# POWER_SUPPLY_BOARD.net
KiCad netlist of a schematic drawn in EAGLE
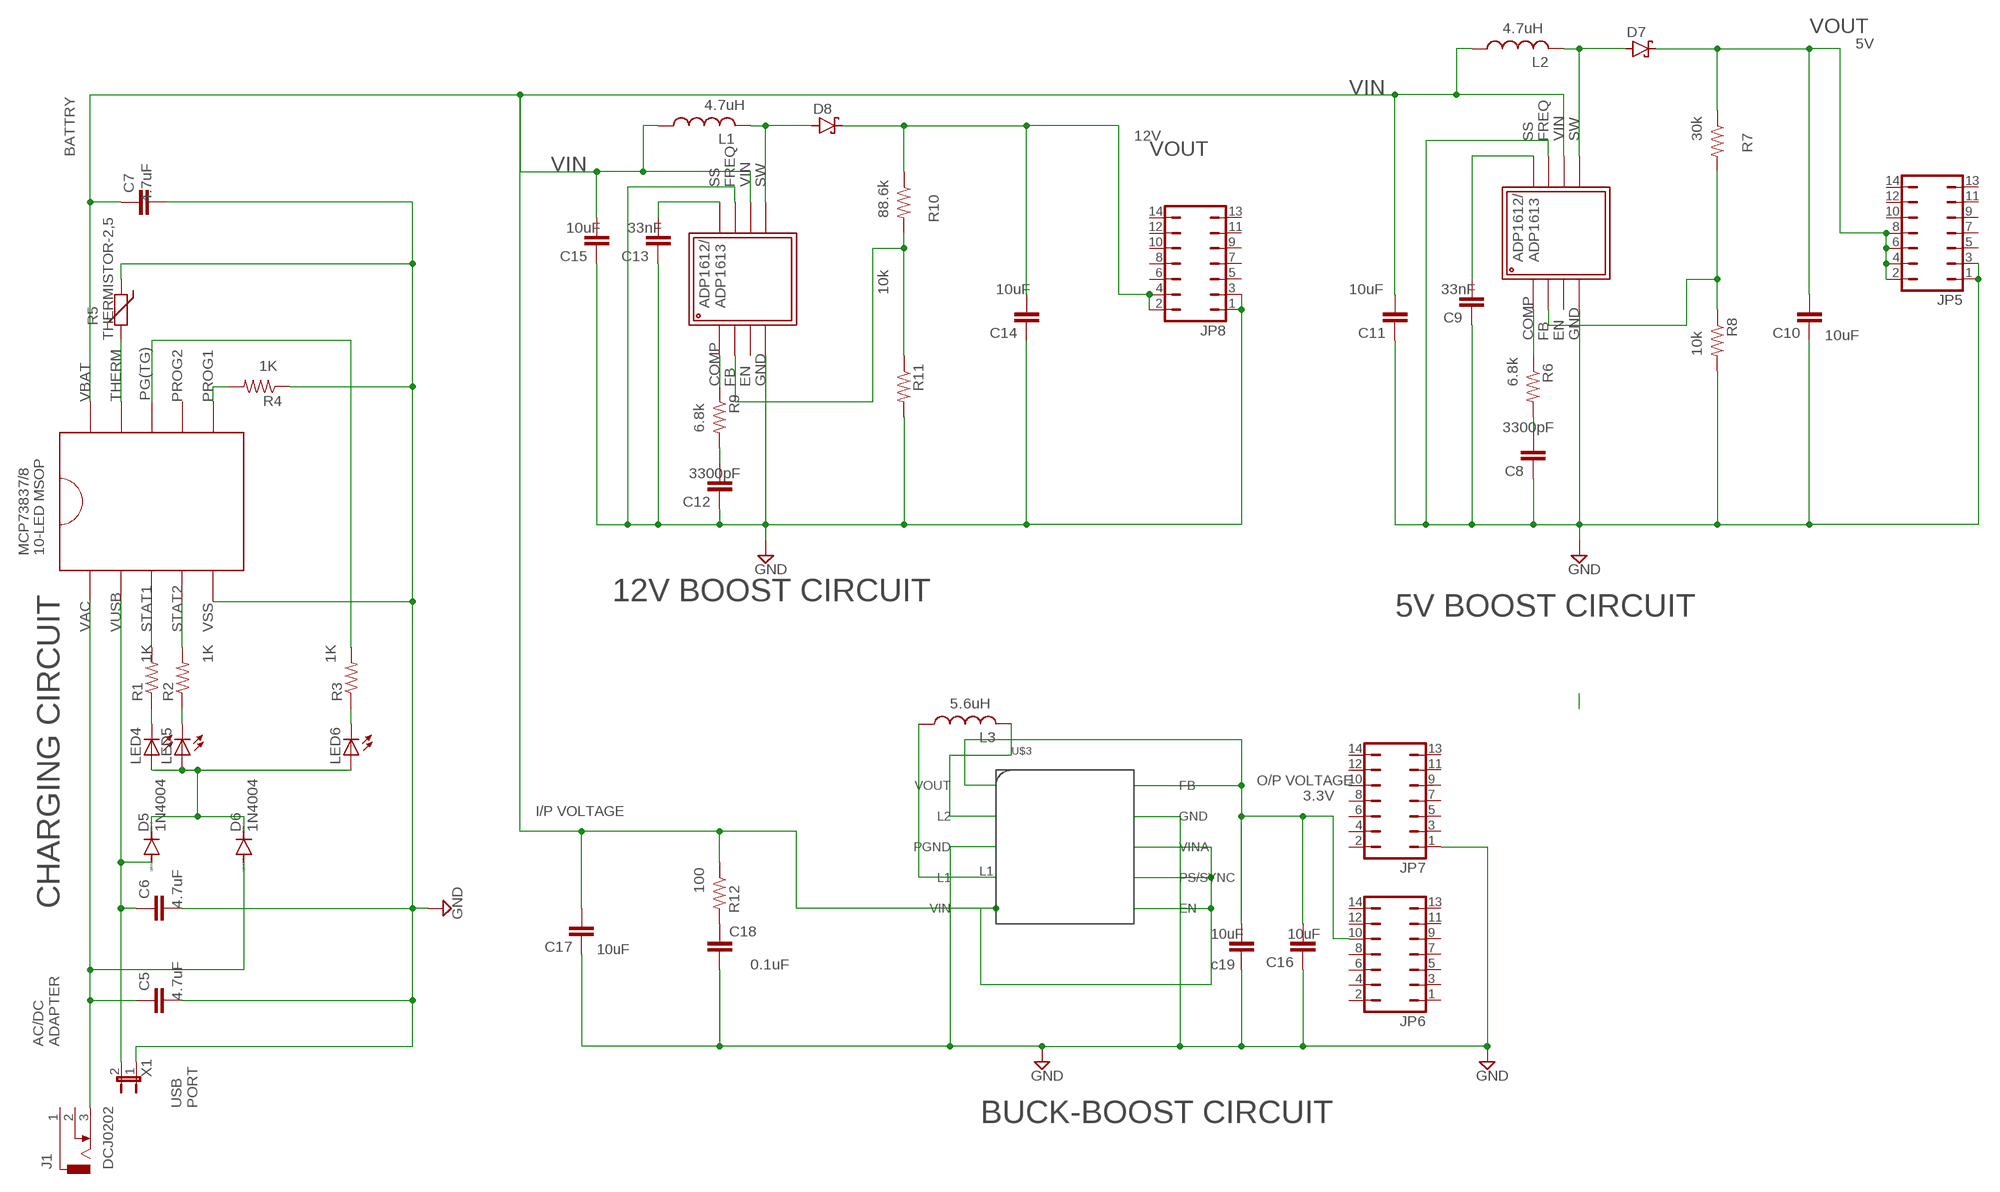
[diagram p0: schematic, sheet 1]

(export (version "E")
  (design (tool "Eeschema 10.0.6"))
  (components
    (comp (ref "C1")
      (value "C2,5-3")
      (footprint "eagle-import:C2.5-3")
      (libsource (lib "eagle-import") (part "C2,5-3"))
    )
    (comp (ref "C5")
      (value "C2.5/5")
      (footprint "eagle-import:C2.5-5")
      (libsource (lib "eagle-import") (part "C2.5/5"))
    )
    (comp (ref "C6")
      (value "C2.5/5")
      (footprint "eagle-import:C2.5-5")
      (libsource (lib "eagle-import") (part "C2.5/5"))
    )
    (comp (ref "C7")
      (value "C2.5/5")
      (footprint "eagle-import:C2.5-5")
      (libsource (lib "eagle-import") (part "C2.5/5"))
    )
    (comp (ref "C8")
      (value "C2,5-3")
      (footprint "eagle-import:C2.5-3")
      (libsource (lib "eagle-import") (part "C2,5-3"))
    )
    (comp (ref "C9")
      (value "C2,5-3")
      (footprint "eagle-import:C2.5-3")
      (libsource (lib "eagle-import") (part "C2,5-3"))
    )
    (comp (ref "C10")
      (value "C2,5-3")
      (footprint "eagle-import:C2.5-3")
      (libsource (lib "eagle-import") (part "C2,5-3"))
    )
    (comp (ref "C11")
      (value "C2,5-3")
      (footprint "eagle-import:C2.5-3")
      (libsource (lib "eagle-import") (part "C2,5-3"))
    )
    (comp (ref "C12")
      (value "C2,5-3")
      (footprint "eagle-import:C2.5-3")
      (libsource (lib "eagle-import") (part "C2,5-3"))
    )
    (comp (ref "C13")
      (value "C2,5-3")
      (footprint "eagle-import:C2.5-3")
      (libsource (lib "eagle-import") (part "C2,5-3"))
    )
    (comp (ref "C14")
      (value "C2,5-3")
      (footprint "eagle-import:C2.5-3")
      (libsource (lib "eagle-import") (part "C2,5-3"))
    )
    (comp (ref "C15")
      (value "C2,5-3")
      (footprint "eagle-import:C2.5-3")
      (libsource (lib "eagle-import") (part "C2,5-3"))
    )
    (comp (ref "C16")
      (value "C2,5-3")
      (footprint "eagle-import:C2.5-3")
      (libsource (lib "eagle-import") (part "C2,5-3"))
    )
    (comp (ref "C17")
      (value "C2,5-3")
      (footprint "eagle-import:C2.5-3")
      (libsource (lib "eagle-import") (part "C2,5-3"))
    )
    (comp (ref "C18")
      (value "C2,5-3")
      (footprint "eagle-import:C2.5-3")
      (libsource (lib "eagle-import") (part "C2,5-3"))
    )
    (comp (ref "D5")
      (value "1N4004")
      (footprint "eagle-import:DO41-10")
      (libsource (lib "eagle-import") (part "1N4004"))
    )
    (comp (ref "D6")
      (value "1N4004")
      (footprint "eagle-import:DO41-10")
      (libsource (lib "eagle-import") (part "1N4004"))
    )
    (comp (ref "D7")
      (value "SCHOTTKY-DIODEC4111-15")
      (footprint "eagle-import:C4111-15")
      (libsource (lib "eagle-import") (part "SCHOTTKY-DIODEC4111-15"))
    )
    (comp (ref "D8")
      (value "SCHOTTKY-DIODEC4111-15")
      (footprint "eagle-import:C4111-15")
      (libsource (lib "eagle-import") (part "SCHOTTKY-DIODEC4111-15"))
    )
    (comp (ref "J1")
      (value "DCJ0202")
      (footprint "eagle-import:DCJ0202")
      (libsource (lib "eagle-import") (part "DCJ0202"))
    )
    (comp (ref "JP1")
      (value "JP1E")
      (footprint "eagle-import:JP1")
      (libsource (lib "eagle-import") (part "JP1E"))
    )
    (comp (ref "JP5")
      (value "JP7Q")
      (footprint "eagle-import:JP7Q")
      (libsource (lib "eagle-import") (part "JP7Q"))
    )
    (comp (ref "JP6")
      (value "JP7Q")
      (footprint "eagle-import:JP7Q")
      (libsource (lib "eagle-import") (part "JP7Q"))
    )
    (comp (ref "JP7")
      (value "JP7Q")
      (footprint "eagle-import:JP7Q")
      (libsource (lib "eagle-import") (part "JP7Q"))
    )
    (comp (ref "JP8")
      (value "JP7Q")
      (footprint "eagle-import:JP7Q")
      (libsource (lib "eagle-import") (part "JP7Q"))
    )
    (comp (ref "L1")
      (value "L-US0204/5")
      (footprint "eagle-import:0204_5")
      (libsource (lib "eagle-import") (part "L-US0204/5"))
    )
    (comp (ref "L2")
      (value "L-US0204/5")
      (footprint "eagle-import:0204_5")
      (libsource (lib "eagle-import") (part "L-US0204/5"))
    )
    (comp (ref "L3")
      (value "L-US0204/5")
      (footprint "eagle-import:0204_5")
      (libsource (lib "eagle-import") (part "L-US0204/5"))
    )
    (comp (ref "LED4")
      (value "LED3MM")
      (footprint "eagle-import:LED3MM")
      (libsource (lib "eagle-import") (part "LED3MM"))
    )
    (comp (ref "LED5")
      (value "LED3MM")
      (footprint "eagle-import:LED3MM")
      (libsource (lib "eagle-import") (part "LED3MM"))
    )
    (comp (ref "LED6")
      (value "LED3MM")
      (footprint "eagle-import:LED3MM")
      (libsource (lib "eagle-import") (part "LED3MM"))
    )
    (comp (ref "R1")
      (value "R-US_0204/2V")
      (footprint "eagle-import:0204V")
      (libsource (lib "eagle-import") (part "R-US_0204/2V"))
    )
    (comp (ref "R2")
      (value "R-US_0204/2V")
      (footprint "eagle-import:0204V")
      (libsource (lib "eagle-import") (part "R-US_0204/2V"))
    )
    (comp (ref "R3")
      (value "R-US_0204/2V")
      (footprint "eagle-import:0204V")
      (libsource (lib "eagle-import") (part "R-US_0204/2V"))
    )
    (comp (ref "R4")
      (value "R-US_0204/2V")
      (footprint "eagle-import:0204V")
      (libsource (lib "eagle-import") (part "R-US_0204/2V"))
    )
    (comp (ref "R5")
      (value "THERMISTOR-2,5")
      (footprint "eagle-import:RS-2,5")
      (libsource (lib "eagle-import") (part "THERMISTOR-2,5"))
    )
    (comp (ref "R6")
      (value "R-US_0204/2V")
      (footprint "eagle-import:0204V")
      (libsource (lib "eagle-import") (part "R-US_0204/2V"))
    )
    (comp (ref "R7")
      (value "R-US_0204/2V")
      (footprint "eagle-import:0204V")
      (libsource (lib "eagle-import") (part "R-US_0204/2V"))
    )
    (comp (ref "R8")
      (value "R-US_0204/2V")
      (footprint "eagle-import:0204V")
      (libsource (lib "eagle-import") (part "R-US_0204/2V"))
    )
    (comp (ref "R9")
      (value "R-US_0204/2V")
      (footprint "eagle-import:0204V")
      (libsource (lib "eagle-import") (part "R-US_0204/2V"))
    )
    (comp (ref "R10")
      (value "R-US_0204/2V")
      (footprint "eagle-import:0204V")
      (libsource (lib "eagle-import") (part "R-US_0204/2V"))
    )
    (comp (ref "R11")
      (value "R-US_0204/2V")
      (footprint "eagle-import:0204V")
      (libsource (lib "eagle-import") (part "R-US_0204/2V"))
    )
    (comp (ref "R12")
      (value "R-US_0204/2V")
      (footprint "eagle-import:0204V")
      (libsource (lib "eagle-import") (part "R-US_0204/2V"))
    )
    (comp (ref "U$1")
      (value "ADP1612")
      (footprint "eagle-import:ADP1612")
      (libsource (lib "eagle-import") (part "ADP1612"))
    )
    (comp (ref "U$2")
      (value "ADP1612")
      (footprint "eagle-import:ADP1612")
      (libsource (lib "eagle-import") (part "ADP1612"))
    )
    (comp (ref "U$3")
      (value "TPS63002")
      (footprint "eagle-import:TPS63002")
      (libsource (lib "eagle-import") (part "TPS63002"))
    )
    (comp (ref "U$4")
      (value "MCP73837/8")
      (footprint "eagle-import:MCP73837_8")
      (libsource (lib "eagle-import") (part "MCP73837/8"))
    )
  )
  (nets
    (net (code "1") (name "GND") (class "Default")
      (node (ref "C1") (pin "1") (pinfunction "1_1") (pintype "passive"))
      (node (ref "C10") (pin "1") (pinfunction "1_1") (pintype "passive"))
      (node (ref "C11") (pin "1") (pinfunction "1_1") (pintype "passive"))
      (node (ref "C12") (pin "1") (pinfunction "1_1") (pintype "passive"))
      (node (ref "C13") (pin "1") (pinfunction "1_1") (pintype "passive"))
      (node (ref "C14") (pin "1") (pinfunction "1_1") (pintype "passive"))
      (node (ref "C15") (pin "1") (pinfunction "1_1") (pintype "passive"))
      (node (ref "C16") (pin "1") (pinfunction "1_1") (pintype "passive"))
      (node (ref "C17") (pin "1") (pinfunction "1_1") (pintype "passive"))
      (node (ref "C18") (pin "2") (pinfunction "2_2") (pintype "passive"))
      (node (ref "C5") (pin "2") (pinfunction "2_2") (pintype "passive"))
      (node (ref "C6") (pin "2") (pinfunction "2_2") (pintype "passive"))
      (node (ref "C7") (pin "2") (pinfunction "2_2") (pintype "passive"))
      (node (ref "C8") (pin "1") (pinfunction "1_1") (pintype "passive"))
      (node (ref "C9") (pin "1") (pinfunction "1_1") (pintype "passive"))
      (node (ref "JP1") (pin "1") (pinfunction "1_1") (pintype "passive"))
      (node (ref "JP5") (pin "1") (pinfunction "1_1") (pintype "passive"))
      (node (ref "JP5") (pin "3") (pinfunction "3_3") (pintype "passive"))
      (node (ref "JP7") (pin "1") (pinfunction "1_1") (pintype "passive"))
      (node (ref "JP8") (pin "1") (pinfunction "1_1") (pintype "passive"))
      (node (ref "JP8") (pin "3") (pinfunction "3_3") (pintype "passive"))
      (node (ref "R11") (pin "2") (pinfunction "2_2") (pintype "passive"))
      (node (ref "R4") (pin "1") (pinfunction "1_1") (pintype "passive"))
      (node (ref "R5") (pin "1") (pinfunction "1_1") (pintype "passive"))
      (node (ref "R8") (pin "2") (pinfunction "2_2") (pintype "passive"))
      (node (ref "U$1") (pin "P$4") (pinfunction "P$4_P$4") (pintype "bidirectional"))
      (node (ref "U$1") (pin "P$6") (pinfunction "P$6_P$6") (pintype "bidirectional"))
      (node (ref "U$2") (pin "P$4") (pinfunction "P$4_P$4") (pintype "bidirectional"))
      (node (ref "U$2") (pin "P$6") (pinfunction "P$6_P$6") (pintype "bidirectional"))
      (node (ref "U$3") (pin "GND") (pinfunction "GND_GND") (pintype "bidirectional"))
      (node (ref "U$3") (pin "PGND") (pinfunction "PGND_PGND") (pintype "bidirectional"))
      (node (ref "U$4") (pin "P$5") (pinfunction "P$5_P$5") (pintype "bidirectional"))
    )
    (net (code "2") (name "Net-(C1-Pad2)") (class "Default")
      (node (ref "C1") (pin "2") (pinfunction "2_2") (pintype "passive"))
      (node (ref "C16") (pin "2") (pinfunction "2_2") (pintype "passive"))
      (node (ref "JP6") (pin "10") (pinfunction "10_10") (pintype "passive"))
      (node (ref "U$3") (pin "FB") (pinfunction "FB_FB") (pintype "bidirectional"))
      (node (ref "U$3") (pin "VOUT") (pinfunction "VOUT_VOUT") (pintype "bidirectional"))
    )
    (net (code "3") (name "Net-(C5-Pad1)") (class "Default")
      (node (ref "C5") (pin "1") (pinfunction "1_1") (pintype "passive"))
      (node (ref "D6") (pin "A") (pinfunction "A_A") (pintype "passive"))
      (node (ref "J1") (pin "3") (pinfunction "3_3") (pintype "passive"))
      (node (ref "U$4") (pin "P$1") (pinfunction "P$1_P$1") (pintype "bidirectional"))
    )
    (net (code "4") (name "Net-(C6-Pad1)") (class "Default")
      (node (ref "C6") (pin "1") (pinfunction "1_1") (pintype "passive"))
      (node (ref "D5") (pin "A") (pinfunction "A_A") (pintype "passive"))
      (node (ref "JP1") (pin "2") (pinfunction "2_2") (pintype "passive"))
      (node (ref "U$4") (pin "P$2") (pinfunction "P$2_P$2") (pintype "bidirectional"))
    )
    (net (code "5") (name "Net-(C8-Pad2)") (class "Default")
      (node (ref "C8") (pin "2") (pinfunction "2_2") (pintype "passive"))
      (node (ref "R6") (pin "2") (pinfunction "2_2") (pintype "passive"))
    )
    (net (code "6") (name "Net-(C9-Pad2)") (class "Default")
      (node (ref "C9") (pin "2") (pinfunction "2_2") (pintype "passive"))
      (node (ref "U$1") (pin "P$5") (pinfunction "P$5_P$5") (pintype "bidirectional"))
    )
    (net (code "7") (name "Net-(C10-Pad2)") (class "Default")
      (node (ref "C10") (pin "2") (pinfunction "2_2") (pintype "passive"))
      (node (ref "D7") (pin "C") (pinfunction "C_C") (pintype "passive"))
      (node (ref "JP5") (pin "2") (pinfunction "2_2") (pintype "passive"))
      (node (ref "JP5") (pin "4") (pinfunction "4_4") (pintype "passive"))
      (node (ref "JP5") (pin "6") (pinfunction "6_6") (pintype "passive"))
      (node (ref "JP5") (pin "8") (pinfunction "8_8") (pintype "passive"))
      (node (ref "R7") (pin "1") (pinfunction "1_1") (pintype "passive"))
    )
    (net (code "8") (name "Net-(C11-Pad2)") (class "Default")
      (node (ref "C11") (pin "2") (pinfunction "2_2") (pintype "passive"))
      (node (ref "C15") (pin "2") (pinfunction "2_2") (pintype "passive"))
      (node (ref "C17") (pin "2") (pinfunction "2_2") (pintype "passive"))
      (node (ref "C7") (pin "1") (pinfunction "1_1") (pintype "passive"))
      (node (ref "L1") (pin "1") (pinfunction "1_1") (pintype "passive"))
      (node (ref "L2") (pin "1") (pinfunction "1_1") (pintype "passive"))
      (node (ref "R12") (pin "1") (pinfunction "1_1") (pintype "passive"))
      (node (ref "U$1") (pin "P$7") (pinfunction "P$7_P$7") (pintype "bidirectional"))
      (node (ref "U$2") (pin "P$7") (pinfunction "P$7_P$7") (pintype "bidirectional"))
      (node (ref "U$3") (pin "EN") (pinfunction "EN_EN") (pintype "bidirectional"))
      (node (ref "U$3") (pin "PS/SYNC") (pinfunction "PS/SYNC_PS/SYNC") (pintype "bidirectional"))
      (node (ref "U$3") (pin "VIN") (pinfunction "VIN_VIN") (pintype "bidirectional"))
      (node (ref "U$3") (pin "VINA") (pinfunction "VINA_VINA") (pintype "bidirectional"))
      (node (ref "U$4") (pin "P$10") (pinfunction "P$10_P$10") (pintype "bidirectional"))
    )
    (net (code "9") (name "Net-(C12-Pad2)") (class "Default")
      (node (ref "C12") (pin "2") (pinfunction "2_2") (pintype "passive"))
      (node (ref "R9") (pin "2") (pinfunction "2_2") (pintype "passive"))
    )
    (net (code "10") (name "Net-(C13-Pad2)") (class "Default")
      (node (ref "C13") (pin "2") (pinfunction "2_2") (pintype "passive"))
      (node (ref "U$2") (pin "P$5") (pinfunction "P$5_P$5") (pintype "bidirectional"))
    )
    (net (code "11") (name "Net-(C14-Pad2)") (class "Default")
      (node (ref "C14") (pin "2") (pinfunction "2_2") (pintype "passive"))
      (node (ref "D8") (pin "C") (pinfunction "C_C") (pintype "passive"))
      (node (ref "JP8") (pin "2") (pinfunction "2_2") (pintype "passive"))
      (node (ref "JP8") (pin "4") (pinfunction "4_4") (pintype "passive"))
      (node (ref "R10") (pin "1") (pinfunction "1_1") (pintype "passive"))
    )
    (net (code "12") (name "Net-(C18-Pad1)") (class "Default")
      (node (ref "C18") (pin "1") (pinfunction "1_1") (pintype "passive"))
      (node (ref "R12") (pin "2") (pinfunction "2_2") (pintype "passive"))
    )
    (net (code "13") (name "Net-(D5-PadC)") (class "Default")
      (node (ref "D5") (pin "C") (pinfunction "C_C") (pintype "passive"))
      (node (ref "D6") (pin "C") (pinfunction "C_C") (pintype "passive"))
      (node (ref "LED4") (pin "A") (pinfunction "A_A") (pintype "passive"))
      (node (ref "LED5") (pin "A") (pinfunction "A_A") (pintype "passive"))
      (node (ref "LED6") (pin "A") (pinfunction "A_A") (pintype "passive"))
    )
    (net (code "14") (name "Net-(D7-PadA)") (class "Default")
      (node (ref "D7") (pin "A") (pinfunction "A_A") (pintype "passive"))
      (node (ref "L2") (pin "2") (pinfunction "2_2") (pintype "passive"))
      (node (ref "U$1") (pin "P$8") (pinfunction "P$8_P$8") (pintype "bidirectional"))
    )
    (net (code "15") (name "Net-(D8-PadA)") (class "Default")
      (node (ref "D8") (pin "A") (pinfunction "A_A") (pintype "passive"))
      (node (ref "L1") (pin "2") (pinfunction "2_2") (pintype "passive"))
      (node (ref "U$2") (pin "P$8") (pinfunction "P$8_P$8") (pintype "bidirectional"))
    )
    (net (code "16") (name "Net-(L3-Pad1)") (class "Default")
      (node (ref "L3") (pin "1") (pinfunction "1_1") (pintype "passive"))
      (node (ref "U$3") (pin "L1") (pinfunction "L1_L1") (pintype "bidirectional"))
    )
    (net (code "17") (name "Net-(L3-Pad2)") (class "Default")
      (node (ref "L3") (pin "2") (pinfunction "2_2") (pintype "passive"))
      (node (ref "U$3") (pin "L2") (pinfunction "L2_L2") (pintype "bidirectional"))
    )
    (net (code "18") (name "Net-(LED4-C)") (class "Default")
      (node (ref "LED4") (pin "K") (pinfunction "C_K") (pintype "passive"))
      (node (ref "R1") (pin "1") (pinfunction "1_1") (pintype "passive"))
    )
    (net (code "19") (name "Net-(LED5-C)") (class "Default")
      (node (ref "LED5") (pin "K") (pinfunction "C_K") (pintype "passive"))
      (node (ref "R2") (pin "1") (pinfunction "1_1") (pintype "passive"))
    )
    (net (code "20") (name "Net-(LED6-C)") (class "Default")
      (node (ref "LED6") (pin "K") (pinfunction "C_K") (pintype "passive"))
      (node (ref "R3") (pin "1") (pinfunction "1_1") (pintype "passive"))
    )
    (net (code "21") (name "Net-(R1-Pad2)") (class "Default")
      (node (ref "R1") (pin "2") (pinfunction "2_2") (pintype "passive"))
      (node (ref "U$4") (pin "P$3") (pinfunction "P$3_P$3") (pintype "bidirectional"))
    )
    (net (code "22") (name "Net-(R2-Pad2)") (class "Default")
      (node (ref "R2") (pin "2") (pinfunction "2_2") (pintype "passive"))
      (node (ref "U$4") (pin "P$4") (pinfunction "P$4_P$4") (pintype "bidirectional"))
    )
    (net (code "23") (name "Net-(R3-Pad2)") (class "Default")
      (node (ref "R3") (pin "2") (pinfunction "2_2") (pintype "passive"))
      (node (ref "U$4") (pin "P$8") (pinfunction "P$8_P$8") (pintype "bidirectional"))
    )
    (net (code "24") (name "Net-(R4-Pad2)") (class "Default")
      (node (ref "R4") (pin "2") (pinfunction "2_2") (pintype "passive"))
      (node (ref "U$4") (pin "P$6") (pinfunction "P$6_P$6") (pintype "bidirectional"))
    )
    (net (code "25") (name "Net-(R5-Pad2)") (class "Default")
      (node (ref "R5") (pin "2") (pinfunction "2_2") (pintype "passive"))
      (node (ref "U$4") (pin "P$9") (pinfunction "P$9_P$9") (pintype "bidirectional"))
    )
    (net (code "26") (name "Net-(R6-Pad1)") (class "Default")
      (node (ref "R6") (pin "1") (pinfunction "1_1") (pintype "passive"))
      (node (ref "U$1") (pin "P$1") (pinfunction "P$1_P$1") (pintype "bidirectional"))
    )
    (net (code "27") (name "Net-(R7-Pad2)") (class "Default")
      (node (ref "R7") (pin "2") (pinfunction "2_2") (pintype "passive"))
      (node (ref "R8") (pin "1") (pinfunction "1_1") (pintype "passive"))
      (node (ref "U$1") (pin "P$2") (pinfunction "P$2_P$2") (pintype "bidirectional"))
    )
    (net (code "28") (name "Net-(R9-Pad1)") (class "Default")
      (node (ref "R9") (pin "1") (pinfunction "1_1") (pintype "passive"))
      (node (ref "U$2") (pin "P$1") (pinfunction "P$1_P$1") (pintype "bidirectional"))
    )
    (net (code "29") (name "Net-(R10-Pad2)") (class "Default")
      (node (ref "R10") (pin "2") (pinfunction "2_2") (pintype "passive"))
      (node (ref "R11") (pin "1") (pinfunction "1_1") (pintype "passive"))
      (node (ref "U$2") (pin "P$2") (pinfunction "P$2_P$2") (pintype "bidirectional"))
    )
    (net (code "30") (name "unconnected-(J1-Pad1)") (class "Default")
      (node (ref "J1") (pin "1") (pinfunction "1_1") (pintype "passive"))
    )
    (net (code "31") (name "unconnected-(J1-Pad2)") (class "Default")
      (node (ref "J1") (pin "2") (pinfunction "2_2") (pintype "passive"))
    )
    (net (code "32") (name "unconnected-(JP5-Pad5)") (class "Default")
      (node (ref "JP5") (pin "5") (pinfunction "5_5") (pintype "passive"))
    )
    (net (code "33") (name "unconnected-(JP5-Pad7)") (class "Default")
      (node (ref "JP5") (pin "7") (pinfunction "7_7") (pintype "passive"))
    )
    (net (code "34") (name "unconnected-(JP5-Pad9)") (class "Default")
      (node (ref "JP5") (pin "9") (pinfunction "9_9") (pintype "passive"))
    )
    (net (code "35") (name "unconnected-(JP5-Pad10)") (class "Default")
      (node (ref "JP5") (pin "10") (pinfunction "10_10") (pintype "passive"))
    )
    (net (code "36") (name "unconnected-(JP5-Pad11)") (class "Default")
      (node (ref "JP5") (pin "11") (pinfunction "11_11") (pintype "passive"))
    )
    (net (code "37") (name "unconnected-(JP5-Pad12)") (class "Default")
      (node (ref "JP5") (pin "12") (pinfunction "12_12") (pintype "passive"))
    )
    (net (code "38") (name "unconnected-(JP5-Pad13)") (class "Default")
      (node (ref "JP5") (pin "13") (pinfunction "13_13") (pintype "passive"))
    )
    (net (code "39") (name "unconnected-(JP5-Pad14)") (class "Default")
      (node (ref "JP5") (pin "14") (pinfunction "14_14") (pintype "passive"))
    )
    (net (code "40") (name "unconnected-(JP6-Pad1)") (class "Default")
      (node (ref "JP6") (pin "1") (pinfunction "1_1") (pintype "passive"))
    )
    (net (code "41") (name "unconnected-(JP6-Pad2)") (class "Default")
      (node (ref "JP6") (pin "2") (pinfunction "2_2") (pintype "passive"))
    )
    (net (code "42") (name "unconnected-(JP6-Pad3)") (class "Default")
      (node (ref "JP6") (pin "3") (pinfunction "3_3") (pintype "passive"))
    )
    (net (code "43") (name "unconnected-(JP6-Pad4)") (class "Default")
      (node (ref "JP6") (pin "4") (pinfunction "4_4") (pintype "passive"))
    )
    (net (code "44") (name "unconnected-(JP6-Pad5)") (class "Default")
      (node (ref "JP6") (pin "5") (pinfunction "5_5") (pintype "passive"))
    )
    (net (code "45") (name "unconnected-(JP6-Pad6)") (class "Default")
      (node (ref "JP6") (pin "6") (pinfunction "6_6") (pintype "passive"))
    )
    (net (code "46") (name "unconnected-(JP6-Pad7)") (class "Default")
      (node (ref "JP6") (pin "7") (pinfunction "7_7") (pintype "passive"))
    )
    (net (code "47") (name "unconnected-(JP6-Pad8)") (class "Default")
      (node (ref "JP6") (pin "8") (pinfunction "8_8") (pintype "passive"))
    )
    (net (code "48") (name "unconnected-(JP6-Pad9)") (class "Default")
      (node (ref "JP6") (pin "9") (pinfunction "9_9") (pintype "passive"))
    )
    (net (code "49") (name "unconnected-(JP6-Pad11)") (class "Default")
      (node (ref "JP6") (pin "11") (pinfunction "11_11") (pintype "passive"))
    )
    (net (code "50") (name "unconnected-(JP6-Pad12)") (class "Default")
      (node (ref "JP6") (pin "12") (pinfunction "12_12") (pintype "passive"))
    )
    (net (code "51") (name "unconnected-(JP6-Pad13)") (class "Default")
      (node (ref "JP6") (pin "13") (pinfunction "13_13") (pintype "passive"))
    )
    (net (code "52") (name "unconnected-(JP6-Pad14)") (class "Default")
      (node (ref "JP6") (pin "14") (pinfunction "14_14") (pintype "passive"))
    )
    (net (code "53") (name "unconnected-(JP7-Pad2)") (class "Default")
      (node (ref "JP7") (pin "2") (pinfunction "2_2") (pintype "passive"))
    )
    (net (code "54") (name "unconnected-(JP7-Pad3)") (class "Default")
      (node (ref "JP7") (pin "3") (pinfunction "3_3") (pintype "passive"))
    )
    (net (code "55") (name "unconnected-(JP7-Pad4)") (class "Default")
      (node (ref "JP7") (pin "4") (pinfunction "4_4") (pintype "passive"))
    )
    (net (code "56") (name "unconnected-(JP7-Pad5)") (class "Default")
      (node (ref "JP7") (pin "5") (pinfunction "5_5") (pintype "passive"))
    )
    (net (code "57") (name "unconnected-(JP7-Pad6)") (class "Default")
      (node (ref "JP7") (pin "6") (pinfunction "6_6") (pintype "passive"))
    )
    (net (code "58") (name "unconnected-(JP7-Pad7)") (class "Default")
      (node (ref "JP7") (pin "7") (pinfunction "7_7") (pintype "passive"))
    )
    (net (code "59") (name "unconnected-(JP7-Pad8)") (class "Default")
      (node (ref "JP7") (pin "8") (pinfunction "8_8") (pintype "passive"))
    )
    (net (code "60") (name "unconnected-(JP7-Pad9)") (class "Default")
      (node (ref "JP7") (pin "9") (pinfunction "9_9") (pintype "passive"))
    )
    (net (code "61") (name "unconnected-(JP7-Pad10)") (class "Default")
      (node (ref "JP7") (pin "10") (pinfunction "10_10") (pintype "passive"))
    )
    (net (code "62") (name "unconnected-(JP7-Pad11)") (class "Default")
      (node (ref "JP7") (pin "11") (pinfunction "11_11") (pintype "passive"))
    )
    (net (code "63") (name "unconnected-(JP7-Pad12)") (class "Default")
      (node (ref "JP7") (pin "12") (pinfunction "12_12") (pintype "passive"))
    )
    (net (code "64") (name "unconnected-(JP7-Pad13)") (class "Default")
      (node (ref "JP7") (pin "13") (pinfunction "13_13") (pintype "passive"))
    )
    (net (code "65") (name "unconnected-(JP7-Pad14)") (class "Default")
      (node (ref "JP7") (pin "14") (pinfunction "14_14") (pintype "passive"))
    )
    (net (code "66") (name "unconnected-(JP8-Pad5)") (class "Default")
      (node (ref "JP8") (pin "5") (pinfunction "5_5") (pintype "passive"))
    )
    (net (code "67") (name "unconnected-(JP8-Pad6)") (class "Default")
      (node (ref "JP8") (pin "6") (pinfunction "6_6") (pintype "passive"))
    )
    (net (code "68") (name "unconnected-(JP8-Pad7)") (class "Default")
      (node (ref "JP8") (pin "7") (pinfunction "7_7") (pintype "passive"))
    )
    (net (code "69") (name "unconnected-(JP8-Pad8)") (class "Default")
      (node (ref "JP8") (pin "8") (pinfunction "8_8") (pintype "passive"))
    )
    (net (code "70") (name "unconnected-(JP8-Pad9)") (class "Default")
      (node (ref "JP8") (pin "9") (pinfunction "9_9") (pintype "passive"))
    )
    (net (code "71") (name "unconnected-(JP8-Pad10)") (class "Default")
      (node (ref "JP8") (pin "10") (pinfunction "10_10") (pintype "passive"))
    )
    (net (code "72") (name "unconnected-(JP8-Pad11)") (class "Default")
      (node (ref "JP8") (pin "11") (pinfunction "11_11") (pintype "passive"))
    )
    (net (code "73") (name "unconnected-(JP8-Pad12)") (class "Default")
      (node (ref "JP8") (pin "12") (pinfunction "12_12") (pintype "passive"))
    )
    (net (code "74") (name "unconnected-(JP8-Pad13)") (class "Default")
      (node (ref "JP8") (pin "13") (pinfunction "13_13") (pintype "passive"))
    )
    (net (code "75") (name "unconnected-(JP8-Pad14)") (class "Default")
      (node (ref "JP8") (pin "14") (pinfunction "14_14") (pintype "passive"))
    )
    (net (code "76") (name "unconnected-(U$1-PadP$3)") (class "Default")
      (node (ref "U$1") (pin "P$3") (pinfunction "P$3_P$3") (pintype "bidirectional"))
    )
    (net (code "77") (name "unconnected-(U$2-PadP$3)") (class "Default")
      (node (ref "U$2") (pin "P$3") (pinfunction "P$3_P$3") (pintype "bidirectional"))
    )
    (net (code "78") (name "unconnected-(U$4-PadP$7)") (class "Default")
      (node (ref "U$4") (pin "P$7") (pinfunction "P$7_P$7") (pintype "bidirectional"))
    )
  )
)
